# I2Cexpander.net
KiCad netlist of a schematic drawn in Altium Designer
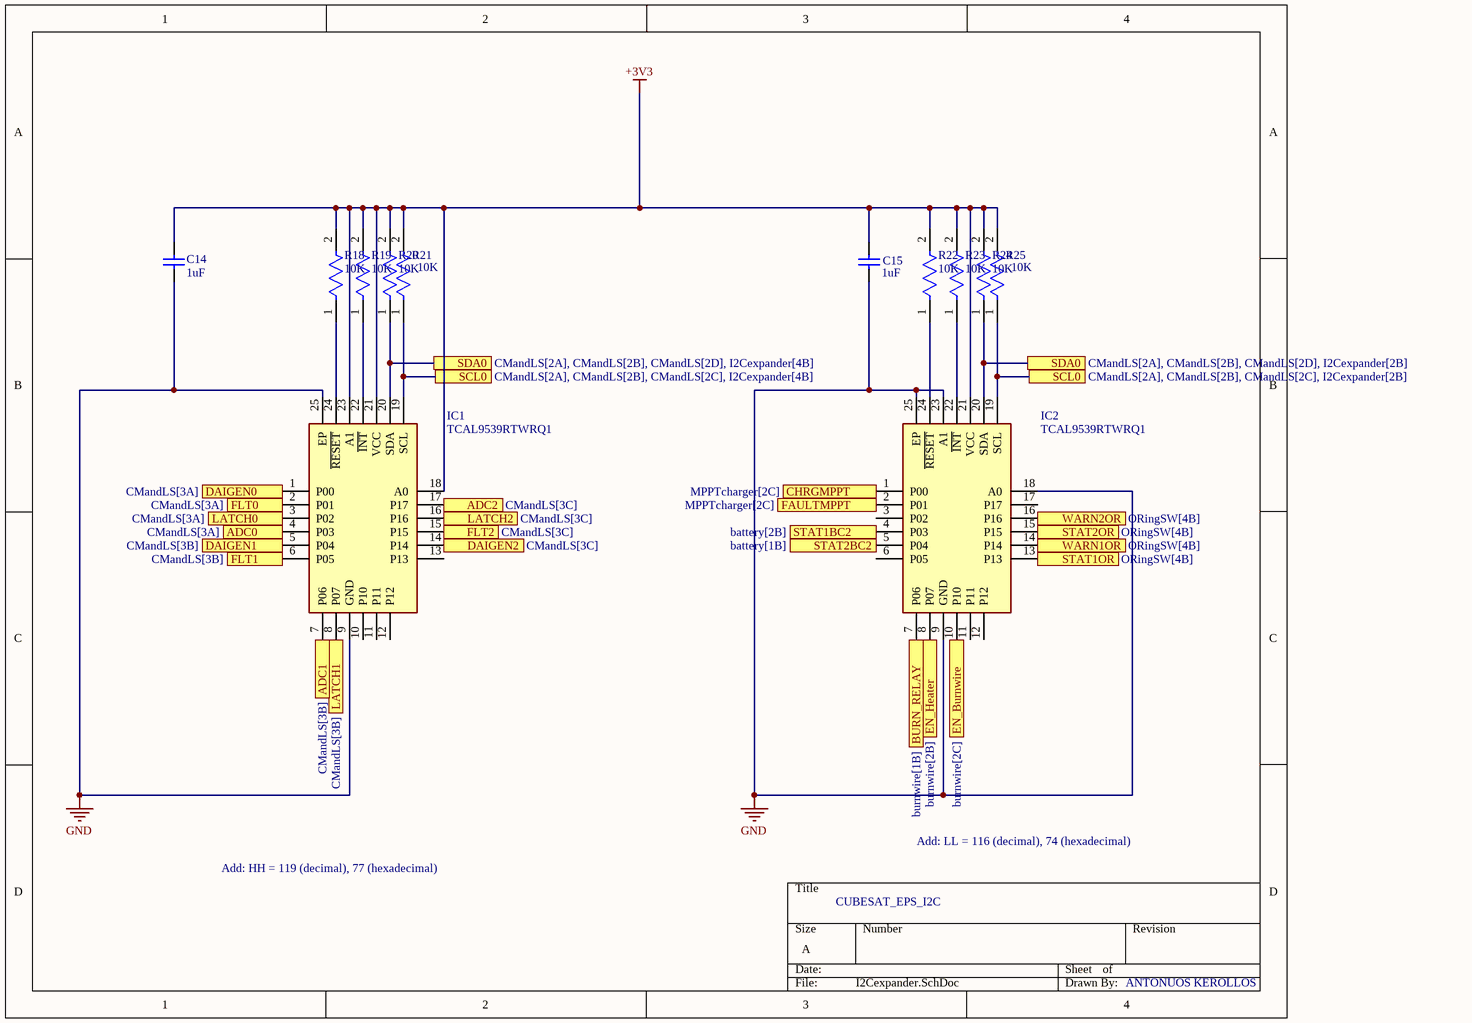
[diagram p0: I2Cexpander.SchDoc]

(export (version "E")
  (design (tool "Eeschema 10.0.6"))
  (components
    (comp (ref "C14")
      (value "1uF")
      (footprint "CAPC2013X140X50LL20T25")
      (fields (field (name "PART NUMBER") "C0805C105K3RACTU") (field (name "MANUFACTURER") "Kemet"))
      (libsource (lib "Altium Content Vault") (part "CAP"))
    )
    (comp (ref "C15")
      (value "1uF")
      (footprint "CAPC2013X140X50LL20T25")
      (fields (field (name "PART NUMBER") "C0805C105K3RACTU") (field (name "MANUFACTURER") "Kemet"))
      (libsource (lib "Altium Content Vault") (part "CAP"))
    )
    (comp (ref "IC1")
      (value "TCAL9539RTWRQ1")
      (footprint "SamacSys:QFN50P400X400X80-25N-D")
      (description "Integrated Circuit")
      (fields (field (name "MOUSER PART NUMBER") "595-TCAL9539RTWRQ1"))
      (libsource (lib "*") (part "TCAL9539RTWRQ1"))
    )
    (comp (ref "IC2")
      (value "TCAL9539RTWRQ1")
      (footprint "SamacSys:QFN50P400X400X80-25N-D")
      (description "Integrated Circuit")
      (fields (field (name "MOUSER PART NUMBER") "595-TCAL9539RTWRQ1"))
      (libsource (lib "*") (part "TCAL9539RTWRQ1"))
    )
    (comp (ref "R18")
      (value "10K")
      (footprint "FP-CRCW0805-e3-IPC_A")
      (description "RES Thick Film, 10kΩ, 1%, 0.125W, 100ppm/°C, 0805")
      (fields (field (name "TOLERANCE") "1%"))
      (libsource (lib "Altium Content Vault") (part "1029c3af85768c4190bb7ad29bc67b5"))
    )
    (comp (ref "R19")
      (value "10K")
      (footprint "FP-CRCW0805-e3-IPC_A")
      (description "RES Thick Film, 10kΩ, 1%, 0.125W, 100ppm/°C, 0805")
      (fields (field (name "TOLERANCE") "1%"))
      (libsource (lib "Altium Content Vault") (part "1029c3af85768c4190bb7ad29bc67b5"))
    )
    (comp (ref "R20")
      (value "10K")
      (footprint "FP-CRCW0805-e3-IPC_A")
      (description "RES Thick Film, 10kΩ, 1%, 0.125W, 100ppm/°C, 0805")
      (fields (field (name "TOLERANCE") "1%"))
      (libsource (lib "Altium Content Vault") (part "1029c3af85768c4190bb7ad29bc67b5"))
    )
    (comp (ref "R21")
      (value "10K")
      (footprint "FP-CRCW0805-e3-IPC_A")
      (description "RES Thick Film, 10kΩ, 1%, 0.125W, 100ppm/°C, 0805")
      (fields (field (name "TOLERANCE") "1%"))
      (libsource (lib "Altium Content Vault") (part "1029c3af85768c4190bb7ad29bc67b5"))
    )
    (comp (ref "R22")
      (value "10K")
      (footprint "FP-CRCW0805-e3-IPC_A")
      (description "RES Thick Film, 10kΩ, 1%, 0.125W, 100ppm/°C, 0805")
      (fields (field (name "TOLERANCE") "1%"))
      (libsource (lib "Altium Content Vault") (part "1029c3af85768c4190bb7ad29bc67b5"))
    )
    (comp (ref "R23")
      (value "10K")
      (footprint "FP-CRCW0805-e3-IPC_A")
      (description "RES Thick Film, 10kΩ, 1%, 0.125W, 100ppm/°C, 0805")
      (fields (field (name "TOLERANCE") "1%"))
      (libsource (lib "Altium Content Vault") (part "1029c3af85768c4190bb7ad29bc67b5"))
    )
    (comp (ref "R24")
      (value "10K")
      (footprint "FP-CRCW0805-e3-IPC_A")
      (description "RES Thick Film, 10kΩ, 1%, 0.125W, 100ppm/°C, 0805")
      (fields (field (name "TOLERANCE") "1%"))
      (libsource (lib "Altium Content Vault") (part "1029c3af85768c4190bb7ad29bc67b5"))
    )
    (comp (ref "R25")
      (value "10K")
      (footprint "FP-CRCW0805-e3-IPC_A")
      (description "RES Thick Film, 10kΩ, 1%, 0.125W, 100ppm/°C, 0805")
      (fields (field (name "TOLERANCE") "1%"))
      (libsource (lib "Altium Content Vault") (part "1029c3af85768c4190bb7ad29bc67b5"))
    )
  )
  (nets
    (net (code "1") (name "+3V3") (class "Default")
      (node (ref "C14") (pin "2") (pinfunction "2_2") (pintype "passive"))
      (node (ref "C15") (pin "2") (pinfunction "2_2") (pintype "passive"))
      (node (ref "IC1") (pin "18") (pinfunction "A0_18") (pintype "passive"))
      (node (ref "IC1") (pin "21") (pinfunction "VCC_21") (pintype "passive"))
      (node (ref "IC1") (pin "23") (pinfunction "A1_23") (pintype "passive"))
      (node (ref "IC2") (pin "21") (pinfunction "VCC_21") (pintype "passive"))
      (node (ref "R18") (pin "2") (pinfunction "2_2") (pintype "passive"))
      (node (ref "R19") (pin "2") (pinfunction "2_2") (pintype "passive"))
      (node (ref "R20") (pin "2") (pinfunction "2_2") (pintype "passive"))
      (node (ref "R21") (pin "2") (pinfunction "2_2") (pintype "passive"))
      (node (ref "R22") (pin "2") (pinfunction "2_2") (pintype "passive"))
      (node (ref "R23") (pin "2") (pinfunction "2_2") (pintype "passive"))
      (node (ref "R24") (pin "2") (pinfunction "2_2") (pintype "passive"))
      (node (ref "R25") (pin "2") (pinfunction "2_2") (pintype "passive"))
    )
    (net (code "2") (name "/ADC0") (class "Default")
      (node (ref "IC1") (pin "4") (pinfunction "P03_4") (pintype "passive"))
    )
    (net (code "3") (name "/ADC1") (class "Default")
      (node (ref "IC1") (pin "7") (pinfunction "P06_7") (pintype "passive"))
    )
    (net (code "4") (name "/ADC2") (class "Default")
      (node (ref "IC1") (pin "17") (pinfunction "P17_17") (pintype "passive"))
    )
    (net (code "5") (name "/BURN_RELAY") (class "Default")
      (node (ref "IC2") (pin "7") (pinfunction "P06_7") (pintype "passive"))
    )
    (net (code "6") (name "/CHRGMPPT") (class "Default")
      (node (ref "IC2") (pin "1") (pinfunction "P00_1") (pintype "passive"))
    )
    (net (code "7") (name "/DAIGEN0") (class "Default")
      (node (ref "IC1") (pin "1") (pinfunction "P00_1") (pintype "passive"))
    )
    (net (code "8") (name "/DAIGEN1") (class "Default")
      (node (ref "IC1") (pin "5") (pinfunction "P04_5") (pintype "passive"))
    )
    (net (code "9") (name "/DAIGEN2") (class "Default")
      (node (ref "IC1") (pin "14") (pinfunction "P14_14") (pintype "passive"))
    )
    (net (code "10") (name "/EN_Burnwire") (class "Default")
      (node (ref "IC2") (pin "10") (pinfunction "P10_10") (pintype "passive"))
    )
    (net (code "11") (name "/EN_Heater") (class "Default")
      (node (ref "IC2") (pin "8") (pinfunction "P07_8") (pintype "passive"))
    )
    (net (code "12") (name "/FAULTMPPT") (class "Default")
      (node (ref "IC2") (pin "2") (pinfunction "P01_2") (pintype "passive"))
    )
    (net (code "13") (name "/FLT0") (class "Default")
      (node (ref "IC1") (pin "2") (pinfunction "P01_2") (pintype "passive"))
    )
    (net (code "14") (name "/FLT1") (class "Default")
      (node (ref "IC1") (pin "6") (pinfunction "P05_6") (pintype "passive"))
    )
    (net (code "15") (name "/FLT2") (class "Default")
      (node (ref "IC1") (pin "15") (pinfunction "P15_15") (pintype "passive"))
    )
    (net (code "16") (name "/LATCH0") (class "Default")
      (node (ref "IC1") (pin "3") (pinfunction "P02_3") (pintype "passive"))
    )
    (net (code "17") (name "/LATCH1") (class "Default")
      (node (ref "IC1") (pin "8") (pinfunction "P07_8") (pintype "passive"))
    )
    (net (code "18") (name "/LATCH2") (class "Default")
      (node (ref "IC1") (pin "16") (pinfunction "P16_16") (pintype "passive"))
    )
    (net (code "19") (name "/SCL0") (class "Default")
      (node (ref "IC1") (pin "19") (pinfunction "SCL_19") (pintype "passive"))
      (node (ref "IC2") (pin "19") (pinfunction "SCL_19") (pintype "passive"))
      (node (ref "R21") (pin "1") (pinfunction "1_1") (pintype "passive"))
      (node (ref "R25") (pin "1") (pinfunction "1_1") (pintype "passive"))
    )
    (net (code "20") (name "/SDA0") (class "Default")
      (node (ref "IC1") (pin "20") (pinfunction "SDA_20") (pintype "passive"))
      (node (ref "IC2") (pin "20") (pinfunction "SDA_20") (pintype "passive"))
      (node (ref "R20") (pin "1") (pinfunction "1_1") (pintype "passive"))
      (node (ref "R24") (pin "1") (pinfunction "1_1") (pintype "passive"))
    )
    (net (code "21") (name "/STAT1BC2") (class "Default")
      (node (ref "IC2") (pin "4") (pinfunction "P03_4") (pintype "passive"))
    )
    (net (code "22") (name "/STAT1OR") (class "Default")
      (node (ref "IC2") (pin "13") (pinfunction "P13_13") (pintype "passive"))
    )
    (net (code "23") (name "/STAT2BC2") (class "Default")
      (node (ref "IC2") (pin "5") (pinfunction "P04_5") (pintype "passive"))
    )
    (net (code "24") (name "/STAT2OR") (class "Default")
      (node (ref "IC2") (pin "15") (pinfunction "P15_15") (pintype "passive"))
    )
    (net (code "25") (name "/WARN1OR") (class "Default")
      (node (ref "IC2") (pin "14") (pinfunction "P14_14") (pintype "passive"))
    )
    (net (code "26") (name "/WARN2OR") (class "Default")
      (node (ref "IC2") (pin "16") (pinfunction "P16_16") (pintype "passive"))
    )
    (net (code "27") (name "GND") (class "Default")
      (node (ref "C14") (pin "1") (pinfunction "1_1") (pintype "passive"))
      (node (ref "C15") (pin "1") (pinfunction "1_1") (pintype "passive"))
      (node (ref "IC1") (pin "25") (pinfunction "EP_25") (pintype "passive"))
      (node (ref "IC1") (pin "9") (pinfunction "GND_9") (pintype "passive"))
      (node (ref "IC2") (pin "18") (pinfunction "A0_18") (pintype "passive"))
      (node (ref "IC2") (pin "23") (pinfunction "A1_23") (pintype "passive"))
      (node (ref "IC2") (pin "25") (pinfunction "EP_25") (pintype "passive"))
      (node (ref "IC2") (pin "9") (pinfunction "GND_9") (pintype "passive"))
    )
    (net (code "28") (name "Net-(IC1-~{INT})") (class "Default")
      (node (ref "IC1") (pin "22") (pinfunction "~{INT}_22") (pintype "passive"))
      (node (ref "R19") (pin "1") (pinfunction "1_1") (pintype "passive"))
    )
    (net (code "29") (name "Net-(IC1-~{RESET})") (class "Default")
      (node (ref "IC1") (pin "24") (pinfunction "~{RESET}_24") (pintype "passive"))
      (node (ref "R18") (pin "1") (pinfunction "1_1") (pintype "passive"))
    )
    (net (code "30") (name "Net-(IC2-~{INT})") (class "Default")
      (node (ref "IC2") (pin "22") (pinfunction "~{INT}_22") (pintype "passive"))
      (node (ref "R23") (pin "1") (pinfunction "1_1") (pintype "passive"))
    )
    (net (code "31") (name "Net-(IC2-~{RESET})") (class "Default")
      (node (ref "IC2") (pin "24") (pinfunction "~{RESET}_24") (pintype "passive"))
      (node (ref "R22") (pin "1") (pinfunction "1_1") (pintype "passive"))
    )
    (net (code "32") (name "unconnected-(IC1-P10-Pad10)") (class "Default")
      (node (ref "IC1") (pin "10") (pinfunction "P10_10") (pintype "passive"))
    )
    (net (code "33") (name "unconnected-(IC1-P11-Pad11)") (class "Default")
      (node (ref "IC1") (pin "11") (pinfunction "P11_11") (pintype "passive"))
    )
    (net (code "34") (name "unconnected-(IC1-P12-Pad12)") (class "Default")
      (node (ref "IC1") (pin "12") (pinfunction "P12_12") (pintype "passive"))
    )
    (net (code "35") (name "unconnected-(IC1-P13-Pad13)") (class "Default")
      (node (ref "IC1") (pin "13") (pinfunction "P13_13") (pintype "passive"))
    )
    (net (code "36") (name "unconnected-(IC2-P02-Pad3)") (class "Default")
      (node (ref "IC2") (pin "3") (pinfunction "P02_3") (pintype "passive"))
    )
    (net (code "37") (name "unconnected-(IC2-P05-Pad6)") (class "Default")
      (node (ref "IC2") (pin "6") (pinfunction "P05_6") (pintype "passive"))
    )
    (net (code "38") (name "unconnected-(IC2-P11-Pad11)") (class "Default")
      (node (ref "IC2") (pin "11") (pinfunction "P11_11") (pintype "passive"))
    )
    (net (code "39") (name "unconnected-(IC2-P12-Pad12)") (class "Default")
      (node (ref "IC2") (pin "12") (pinfunction "P12_12") (pintype "passive"))
    )
    (net (code "40") (name "unconnected-(IC2-P17-Pad17)") (class "Default")
      (node (ref "IC2") (pin "17") (pinfunction "P17_17") (pintype "passive"))
    )
  )
)
